# IR_LED.net
KiCad netlist of a schematic drawn in Altium Designer
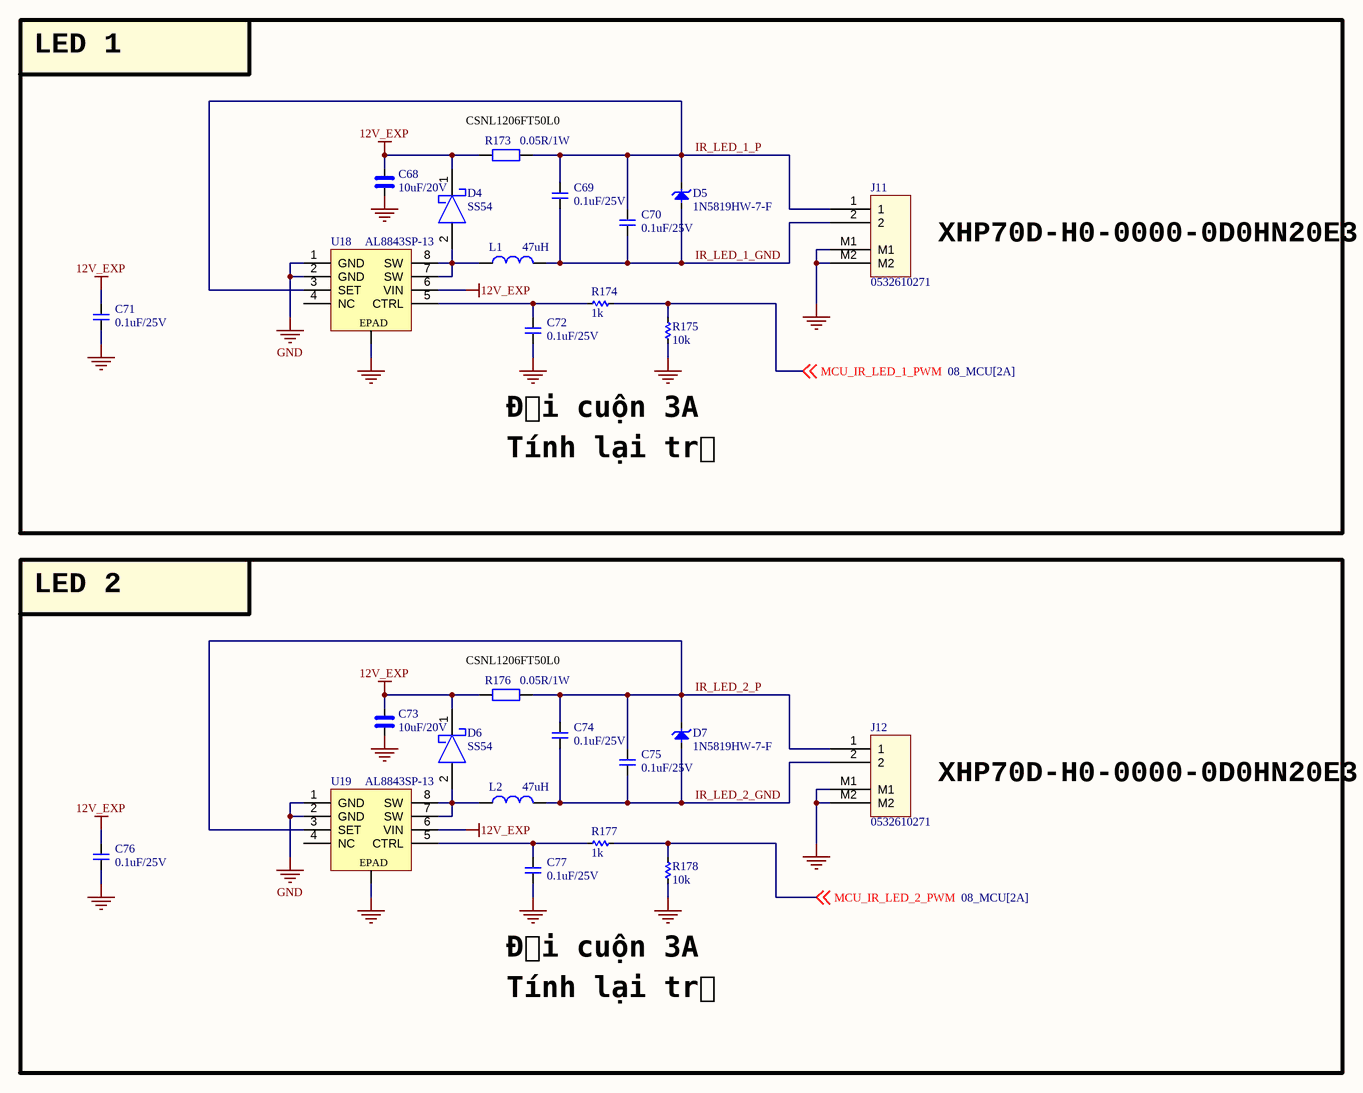
[diagram p0: IR_LED.SchDoc]

(export (version "E")
  (design (tool "Eeschema 10.0.6"))
  (components
    (comp (ref "C68")
      (value "10uF/20V")
      (footprint "CAP_C_2012X110")
      (description "CAP High Value")
      (libsource (lib "LABLIB") (part "_CAP_C_High_2"))
    )
    (comp (ref "C69")
      (value "0.1uF/25V")
      (footprint "CAP_C_1608X80")
      (description "CAP")
      (libsource (lib "LABLIB") (part "_CAP_C_2"))
    )
    (comp (ref "C70")
      (value "0.1uF/25V")
      (footprint "CAP_C_1608X80")
      (description "CAP")
      (libsource (lib "LABLIB") (part "_CAP_C_2"))
    )
    (comp (ref "C71")
      (value "0.1uF/25V")
      (footprint "CAP_C_1608X80")
      (description "CAP")
      (libsource (lib "LABLIB") (part "_CAP_C_2"))
    )
    (comp (ref "C72")
      (value "0.1uF/25V")
      (footprint "CAP_C_1608X80")
      (description "CAP")
      (libsource (lib "LABLIB") (part "_CAP_C_2"))
    )
    (comp (ref "C73")
      (value "10uF/20V")
      (footprint "CAP_C_2012X110")
      (description "CAP High Value")
      (libsource (lib "LABLIB") (part "_CAP_C_High_2"))
    )
    (comp (ref "C74")
      (value "0.1uF/25V")
      (footprint "CAP_C_1608X80")
      (description "CAP")
      (libsource (lib "LABLIB") (part "_CAP_C_2"))
    )
    (comp (ref "C75")
      (value "0.1uF/25V")
      (footprint "CAP_C_1608X80")
      (description "CAP")
      (libsource (lib "LABLIB") (part "_CAP_C_2"))
    )
    (comp (ref "C76")
      (value "0.1uF/25V")
      (footprint "CAP_C_1608X80")
      (description "CAP")
      (libsource (lib "LABLIB") (part "_CAP_C_2"))
    )
    (comp (ref "C77")
      (value "0.1uF/25V")
      (footprint "CAP_C_1608X80")
      (description "CAP")
      (libsource (lib "LABLIB") (part "_CAP_C_2"))
    )
    (comp (ref "D4")
      (value "SS54")
      (footprint "DO-214AC_SMA")
      (description "DIODE SCHOTTKY 60V 3A DO214AA")
      (libsource (lib "EXP_HW_V3") (part "SS54"))
    )
    (comp (ref "D5")
      (value "1N5819HW-7-F")
      (footprint "SOD3717X145N")
      (description "Zenner")
      (libsource (lib "LABLIB") (part "DIODE Zener"))
    )
    (comp (ref "D6")
      (value "SS54")
      (footprint "DO-214AC_SMA")
      (description "DIODE SCHOTTKY 60V 3A DO214AA")
      (libsource (lib "EXP_HW_V3") (part "SS54"))
    )
    (comp (ref "D7")
      (value "1N5819HW-7-F")
      (footprint "SOD3717X145N")
      (description "Zenner")
      (libsource (lib "LABLIB") (part "DIODE Zener"))
    )
    (comp (ref "J11")
      (value "0532610271")
      (footprint "MOLEX_5040500291")
      (libsource (lib "LABLIB") (part "Header 2x1_2M"))
    )
    (comp (ref "J12")
      (value "0532610271")
      (footprint "MOLEX_5040500291")
      (libsource (lib "LABLIB") (part "Header 2x1_2M"))
    )
    (comp (ref "L1")
      (value "47uH")
      (footprint "IND_MP_1250x1250x850")
      (description "B82477P4473M000")
      (fields
        (field (name "PARTNO") "78477010")
        (field (name "MANUFACTURER") "Wurth Elektronik")
        (field (name "CREATED BY") "Baojun Chen")
      )
      (libsource (lib "EXP_HW_V3") (part "L-SMD-1"))
    )
    (comp (ref "L2")
      (value "47uH")
      (footprint "IND_MP_1250x1250x850")
      (description "B82477P4473M000")
      (fields
        (field (name "PARTNO") "78477010")
        (field (name "MANUFACTURER") "Wurth Elektronik")
        (field (name "CREATED BY") "Baojun Chen")
      )
      (libsource (lib "EXP_HW_V3") (part "L-SMD-1"))
    )
    (comp (ref "R173")
      (value "0.05R/1W")
      (footprint "RES_C_3216X70")
      (description "RES")
      (libsource (lib "LABLIB") (part "_RES"))
    )
    (comp (ref "R174")
      (value "1k")
      (footprint "RES_C_1608X60")
      (description "RES")
      (libsource (lib "LABLIB") (part "_RES_B_2"))
    )
    (comp (ref "R175")
      (value "10k")
      (footprint "RES_C_1608X60")
      (description "RES")
      (libsource (lib "LABLIB") (part "_RES_B_2"))
    )
    (comp (ref "R176")
      (value "0.05R/1W")
      (footprint "RES_C_3216X70")
      (description "RES")
      (libsource (lib "LABLIB") (part "_RES"))
    )
    (comp (ref "R177")
      (value "1k")
      (footprint "RES_C_1608X60")
      (description "RES")
      (libsource (lib "LABLIB") (part "_RES_B_2"))
    )
    (comp (ref "R178")
      (value "10k")
      (footprint "RES_C_1608X60")
      (description "RES")
      (libsource (lib "LABLIB") (part "_RES_B_2"))
    )
    (comp (ref "U18")
      (value "AL8843SP-13")
      (footprint "SOIC127P602X173-8N_EPAD")
      (description "IC LED DRIVER RGLTR PWM 3A 8SO")
      (libsource (lib "BEE-DAL_EXP_sche") (part "AL8843SP-13"))
    )
    (comp (ref "U19")
      (value "AL8843SP-13")
      (footprint "SOIC127P602X173-8N_EPAD")
      (description "IC LED DRIVER RGLTR PWM 3A 8SO")
      (libsource (lib "BEE-DAL_EXP_sche") (part "AL8843SP-13"))
    )
  )
  (nets
    (net (code "1") (name "/IR_LED_1_GND") (class "Default")
      (node (ref "C69") (pin "1") (pinfunction "1_1") (pintype "passive"))
      (node (ref "C70") (pin "1") (pinfunction "1_1") (pintype "passive"))
      (node (ref "D5") (pin "2") (pinfunction "A_2") (pintype "passive"))
      (node (ref "J11") (pin "2") (pinfunction "2_2") (pintype "passive"))
      (node (ref "L1") (pin "2") (pinfunction "2_2") (pintype "passive"))
    )
    (net (code "2") (name "/IR_LED_1_P") (class "Default")
      (node (ref "C69") (pin "2") (pinfunction "2_2") (pintype "passive"))
      (node (ref "C70") (pin "2") (pinfunction "2_2") (pintype "passive"))
      (node (ref "D5") (pin "1") (pinfunction "K_1") (pintype "passive"))
      (node (ref "J11") (pin "1") (pinfunction "1_1") (pintype "passive"))
      (node (ref "R173") (pin "2") (pinfunction "2_2") (pintype "passive"))
      (node (ref "U18") (pin "3") (pinfunction "SET_3") (pintype "passive"))
    )
    (net (code "3") (name "/IR_LED_2_GND") (class "Default")
      (node (ref "C74") (pin "1") (pinfunction "1_1") (pintype "passive"))
      (node (ref "C75") (pin "1") (pinfunction "1_1") (pintype "passive"))
      (node (ref "D7") (pin "2") (pinfunction "A_2") (pintype "passive"))
      (node (ref "J12") (pin "2") (pinfunction "2_2") (pintype "passive"))
      (node (ref "L2") (pin "2") (pinfunction "2_2") (pintype "passive"))
    )
    (net (code "4") (name "/IR_LED_2_P") (class "Default")
      (node (ref "C74") (pin "2") (pinfunction "2_2") (pintype "passive"))
      (node (ref "C75") (pin "2") (pinfunction "2_2") (pintype "passive"))
      (node (ref "D7") (pin "1") (pinfunction "K_1") (pintype "passive"))
      (node (ref "J12") (pin "1") (pinfunction "1_1") (pintype "passive"))
      (node (ref "R176") (pin "2") (pinfunction "2_2") (pintype "passive"))
      (node (ref "U19") (pin "3") (pinfunction "SET_3") (pintype "passive"))
    )
    (net (code "5") (name "12V_EXP") (class "Default")
      (node (ref "C68") (pin "1") (pinfunction "1_1") (pintype "passive"))
      (node (ref "C71") (pin "2") (pinfunction "2_2") (pintype "passive"))
      (node (ref "C73") (pin "1") (pinfunction "1_1") (pintype "passive"))
      (node (ref "C76") (pin "2") (pinfunction "2_2") (pintype "passive"))
      (node (ref "D4") (pin "1") (pinfunction "1_1") (pintype "passive"))
      (node (ref "D6") (pin "1") (pinfunction "1_1") (pintype "passive"))
      (node (ref "R173") (pin "1") (pinfunction "1_1") (pintype "passive"))
      (node (ref "R176") (pin "1") (pinfunction "1_1") (pintype "passive"))
      (node (ref "U18") (pin "6") (pinfunction "VIN_6") (pintype "passive"))
      (node (ref "U19") (pin "6") (pinfunction "VIN_6") (pintype "passive"))
    )
    (net (code "6") (name "GND") (class "Default")
      (node (ref "C68") (pin "2") (pinfunction "2_2") (pintype "passive"))
      (node (ref "C71") (pin "1") (pinfunction "1_1") (pintype "passive"))
      (node (ref "C72") (pin "1") (pinfunction "1_1") (pintype "passive"))
      (node (ref "C73") (pin "2") (pinfunction "2_2") (pintype "passive"))
      (node (ref "C76") (pin "1") (pinfunction "1_1") (pintype "passive"))
      (node (ref "C77") (pin "1") (pinfunction "1_1") (pintype "passive"))
      (node (ref "J11") (pin "M1") (pinfunction "M1_M1") (pintype "passive"))
      (node (ref "J11") (pin "M2") (pinfunction "M2_M2") (pintype "passive"))
      (node (ref "J12") (pin "M1") (pinfunction "M1_M1") (pintype "passive"))
      (node (ref "J12") (pin "M2") (pinfunction "M2_M2") (pintype "passive"))
      (node (ref "R175") (pin "2") (pinfunction "2_2") (pintype "passive"))
      (node (ref "R178") (pin "2") (pinfunction "2_2") (pintype "passive"))
      (node (ref "U18") (pin "1") (pinfunction "GND_1") (pintype "passive"))
      (node (ref "U18") (pin "2") (pinfunction "GND_2") (pintype "passive"))
      (node (ref "U18") (pin "9") (pinfunction "EPAD_9") (pintype "passive"))
      (node (ref "U19") (pin "1") (pinfunction "GND_1") (pintype "passive"))
      (node (ref "U19") (pin "2") (pinfunction "GND_2") (pintype "passive"))
      (node (ref "U19") (pin "9") (pinfunction "EPAD_9") (pintype "passive"))
    )
    (net (code "7") (name "MCU_IR_LED_1_PWM") (class "Default")
      (node (ref "R174") (pin "2") (pinfunction "2_2") (pintype "passive"))
      (node (ref "R175") (pin "1") (pinfunction "1_1") (pintype "passive"))
    )
    (net (code "8") (name "MCU_IR_LED_2_PWM") (class "Default")
      (node (ref "R177") (pin "2") (pinfunction "2_2") (pintype "passive"))
      (node (ref "R178") (pin "1") (pinfunction "1_1") (pintype "passive"))
    )
    (net (code "9") (name "Net-(D4-Pad2)") (class "Default")
      (node (ref "D4") (pin "2") (pinfunction "2_2") (pintype "passive"))
      (node (ref "L1") (pin "1") (pinfunction "1_1") (pintype "passive"))
      (node (ref "U18") (pin "7") (pinfunction "SW_7") (pintype "passive"))
      (node (ref "U18") (pin "8") (pinfunction "SW_8") (pintype "passive"))
    )
    (net (code "10") (name "Net-(D6-Pad2)") (class "Default")
      (node (ref "D6") (pin "2") (pinfunction "2_2") (pintype "passive"))
      (node (ref "L2") (pin "1") (pinfunction "1_1") (pintype "passive"))
      (node (ref "U19") (pin "7") (pinfunction "SW_7") (pintype "passive"))
      (node (ref "U19") (pin "8") (pinfunction "SW_8") (pintype "passive"))
    )
    (net (code "11") (name "Net-(U18-CTRL)") (class "Default")
      (node (ref "C72") (pin "2") (pinfunction "2_2") (pintype "passive"))
      (node (ref "R174") (pin "1") (pinfunction "1_1") (pintype "passive"))
      (node (ref "U18") (pin "5") (pinfunction "CTRL_5") (pintype "passive"))
    )
    (net (code "12") (name "Net-(U19-CTRL)") (class "Default")
      (node (ref "C77") (pin "2") (pinfunction "2_2") (pintype "passive"))
      (node (ref "R177") (pin "1") (pinfunction "1_1") (pintype "passive"))
      (node (ref "U19") (pin "5") (pinfunction "CTRL_5") (pintype "passive"))
    )
    (net (code "13") (name "unconnected-(U18-NC-Pad4)") (class "Default")
      (node (ref "U18") (pin "4") (pinfunction "NC_4") (pintype "passive"))
    )
    (net (code "14") (name "unconnected-(U19-NC-Pad4)") (class "Default")
      (node (ref "U19") (pin "4") (pinfunction "NC_4") (pintype "passive"))
    )
  )
)
